# accessory_40x80_temp.net
KiCad netlist of a schematic drawn in EAGLE
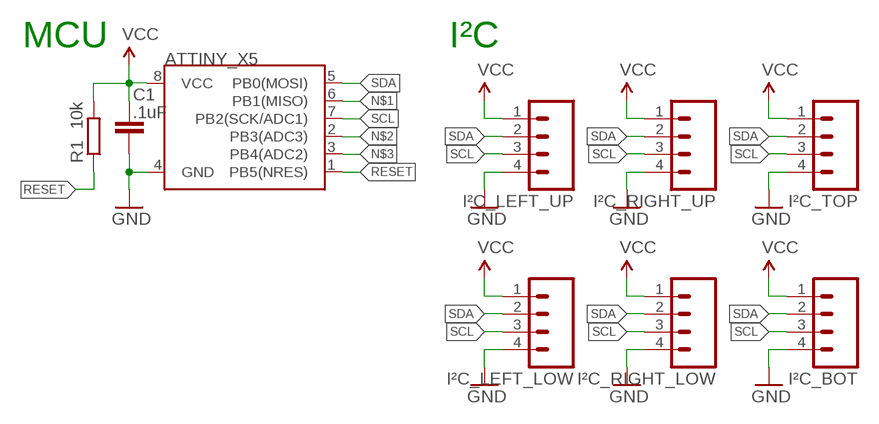
[diagram p0: schematic, sheet 1]

(export (version "E")
  (design (tool "Eeschema 10.0.6"))
  (components
    (comp (ref "ATTINY_X5")
      (value "ATTINY45TINY45-20-SMT")
      (footprint "eagle-import:SO08-EIAJ")
      (libsource (lib "eagle-import") (part "ATTINY45TINY45-20-SMT"))
    )
    (comp (ref "C1")
      (value ".1uF")
      (footprint "eagle-import:C805")
      (libsource (lib "eagle-import") (part "CAPACITOR_NPOL-0805"))
    )
    (comp (ref "I²C_BOT")
      (value "M04PTH")
      (footprint "eagle-import:1X04")
      (libsource (lib "eagle-import") (part "M04PTH"))
    )
    (comp (ref "I²C_LEFT_LOW")
      (value "M04PTH")
      (footprint "eagle-import:1X04")
      (libsource (lib "eagle-import") (part "M04PTH"))
    )
    (comp (ref "I²C_LEFT_UP")
      (value "M04PTH")
      (footprint "eagle-import:1X04")
      (libsource (lib "eagle-import") (part "M04PTH"))
    )
    (comp (ref "I²C_RIGHT_LOW")
      (value "M04PTH")
      (footprint "eagle-import:1X04")
      (libsource (lib "eagle-import") (part "M04PTH"))
    )
    (comp (ref "I²C_RIGHT_UP")
      (value "M04PTH")
      (footprint "eagle-import:1X04")
      (libsource (lib "eagle-import") (part "M04PTH"))
    )
    (comp (ref "I²C_TOP")
      (value "M04PTH")
      (footprint "eagle-import:1X04")
      (libsource (lib "eagle-import") (part "M04PTH"))
    )
    (comp (ref "R1")
      (value "10k")
      (footprint "eagle-import:R805")
      (libsource (lib "eagle-import") (part "RESISTOR-0805R805"))
    )
  )
  (nets
    (net (code "1") (name "GND") (class "Default")
      (node (ref "ATTINY_X5") (pin "4") (pinfunction "GND_4") (pintype "bidirectional"))
      (node (ref "C1") (pin "2") (pinfunction "2_2") (pintype "passive"))
      (node (ref "I²C_BOT") (pin "4") (pinfunction "4_4") (pintype "passive"))
      (node (ref "I²C_LEFT_LOW") (pin "4") (pinfunction "4_4") (pintype "passive"))
      (node (ref "I²C_LEFT_UP") (pin "4") (pinfunction "4_4") (pintype "passive"))
      (node (ref "I²C_RIGHT_LOW") (pin "4") (pinfunction "4_4") (pintype "passive"))
      (node (ref "I²C_RIGHT_UP") (pin "4") (pinfunction "4_4") (pintype "passive"))
      (node (ref "I²C_TOP") (pin "4") (pinfunction "4_4") (pintype "passive"))
    )
    (net (code "2") (name "N$1") (class "Default")
      (node (ref "ATTINY_X5") (pin "6") (pinfunction "PB1(MISO)_6") (pintype "bidirectional"))
    )
    (net (code "3") (name "N$2") (class "Default")
      (node (ref "ATTINY_X5") (pin "2") (pinfunction "PB3(ADC3)_2") (pintype "bidirectional"))
    )
    (net (code "4") (name "N$3") (class "Default")
      (node (ref "ATTINY_X5") (pin "3") (pinfunction "PB4(ADC2)_3") (pintype "bidirectional"))
    )
    (net (code "5") (name "RESET") (class "Default")
      (node (ref "ATTINY_X5") (pin "1") (pinfunction "PB5(NRES)_1") (pintype "bidirectional"))
      (node (ref "R1") (pin "1") (pinfunction "1_1") (pintype "passive"))
    )
    (net (code "6") (name "SCL") (class "Default")
      (node (ref "ATTINY_X5") (pin "7") (pinfunction "PB2(SCK/ADC1)_7") (pintype "bidirectional"))
      (node (ref "I²C_BOT") (pin "3") (pinfunction "3_3") (pintype "passive"))
      (node (ref "I²C_LEFT_LOW") (pin "3") (pinfunction "3_3") (pintype "passive"))
      (node (ref "I²C_LEFT_UP") (pin "3") (pinfunction "3_3") (pintype "passive"))
      (node (ref "I²C_RIGHT_LOW") (pin "3") (pinfunction "3_3") (pintype "passive"))
      (node (ref "I²C_RIGHT_UP") (pin "3") (pinfunction "3_3") (pintype "passive"))
      (node (ref "I²C_TOP") (pin "3") (pinfunction "3_3") (pintype "passive"))
    )
    (net (code "7") (name "SDA") (class "Default")
      (node (ref "ATTINY_X5") (pin "5") (pinfunction "PB0(MOSI)_5") (pintype "bidirectional"))
      (node (ref "I²C_BOT") (pin "2") (pinfunction "2_2") (pintype "passive"))
      (node (ref "I²C_LEFT_LOW") (pin "2") (pinfunction "2_2") (pintype "passive"))
      (node (ref "I²C_LEFT_UP") (pin "2") (pinfunction "2_2") (pintype "passive"))
      (node (ref "I²C_RIGHT_LOW") (pin "2") (pinfunction "2_2") (pintype "passive"))
      (node (ref "I²C_RIGHT_UP") (pin "2") (pinfunction "2_2") (pintype "passive"))
      (node (ref "I²C_TOP") (pin "2") (pinfunction "2_2") (pintype "passive"))
    )
    (net (code "8") (name "VCC") (class "Default")
      (node (ref "ATTINY_X5") (pin "8") (pinfunction "VCC_8") (pintype "bidirectional"))
      (node (ref "C1") (pin "1") (pinfunction "1_1") (pintype "passive"))
      (node (ref "I²C_BOT") (pin "1") (pinfunction "1_1") (pintype "passive"))
      (node (ref "I²C_LEFT_LOW") (pin "1") (pinfunction "1_1") (pintype "passive"))
      (node (ref "I²C_LEFT_UP") (pin "1") (pinfunction "1_1") (pintype "passive"))
      (node (ref "I²C_RIGHT_LOW") (pin "1") (pinfunction "1_1") (pintype "passive"))
      (node (ref "I²C_RIGHT_UP") (pin "1") (pinfunction "1_1") (pintype "passive"))
      (node (ref "I²C_TOP") (pin "1") (pinfunction "1_1") (pintype "passive"))
      (node (ref "R1") (pin "2") (pinfunction "2_2") (pintype "passive"))
    )
  )
)
